# delayed_lfo.net
KiCad netlist of a schematic drawn in EAGLE
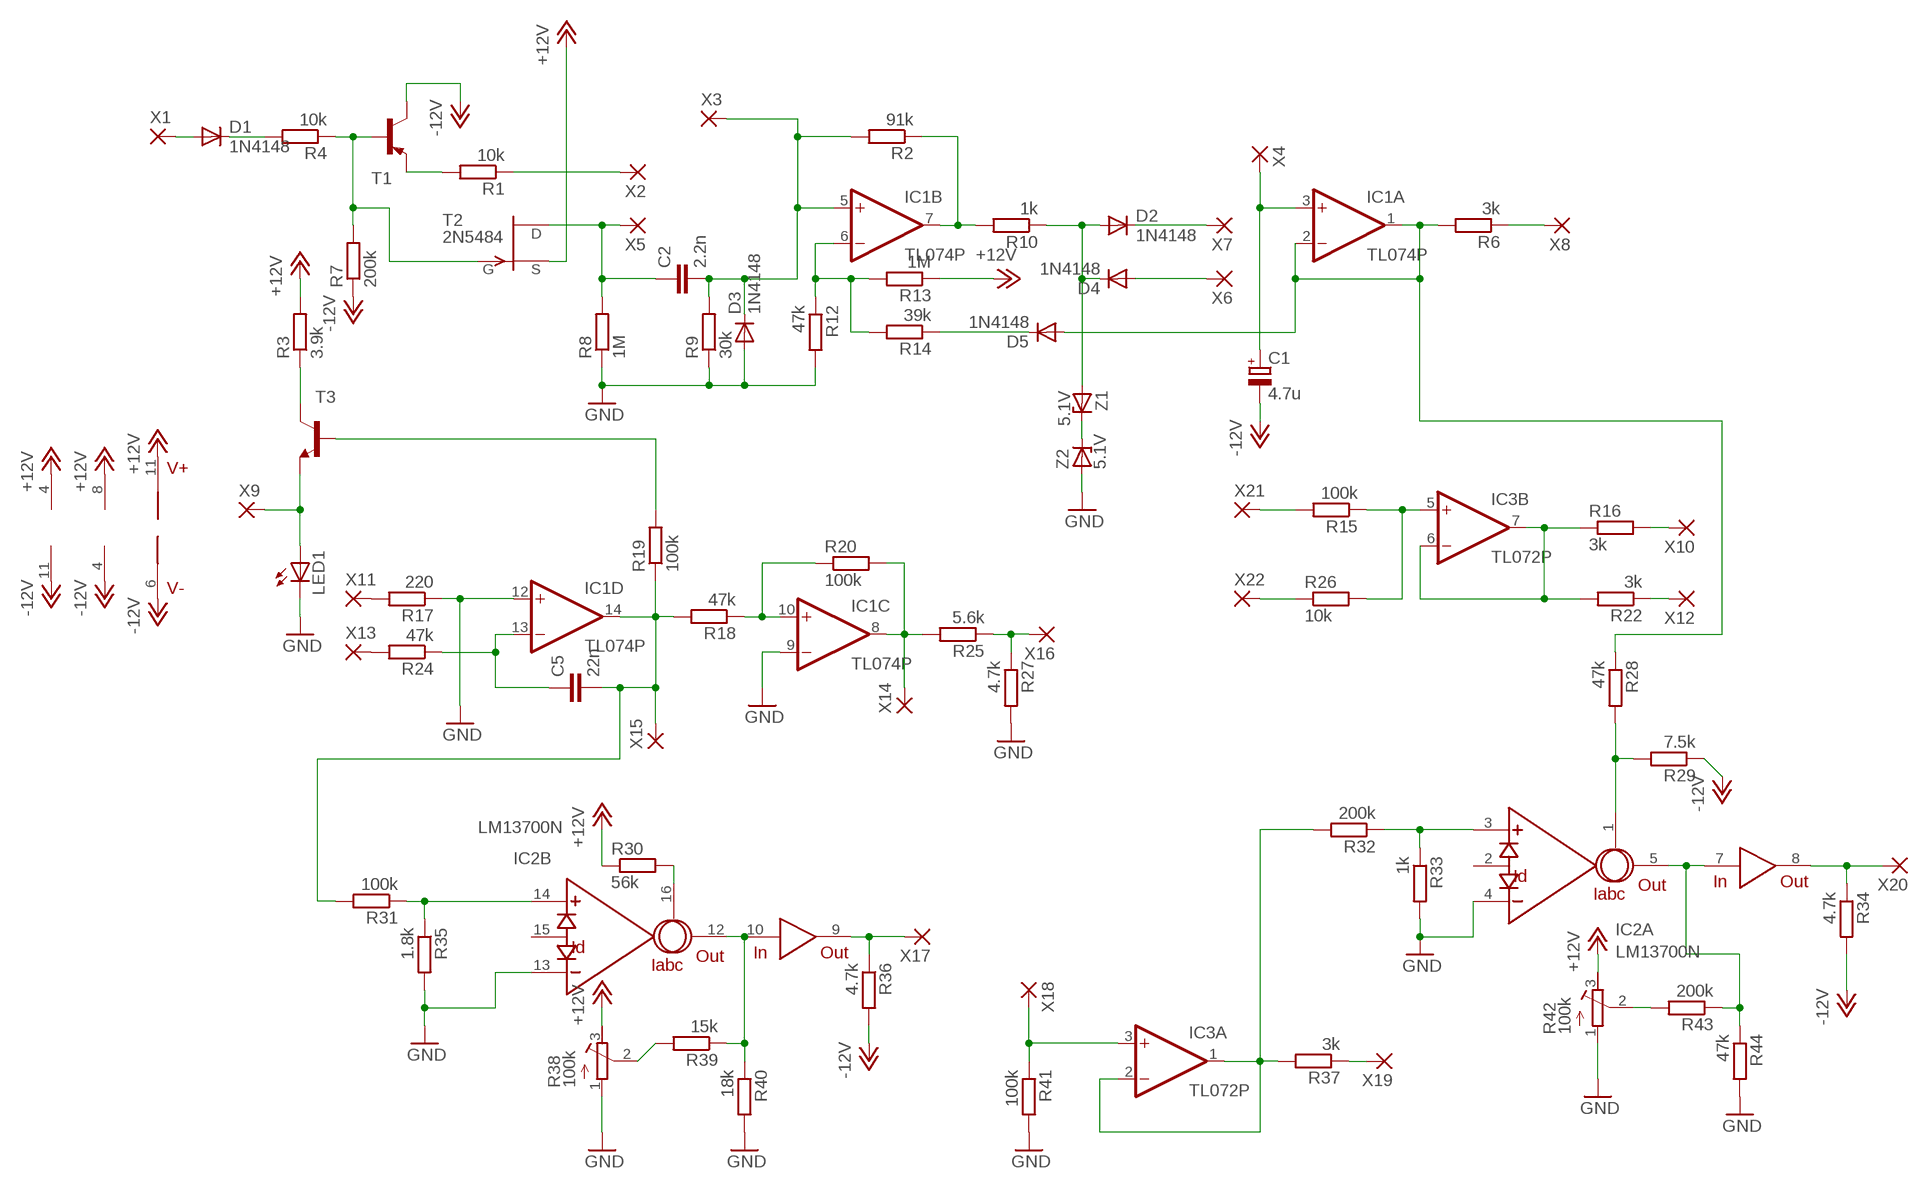
[diagram p0: schematic, sheet 1]
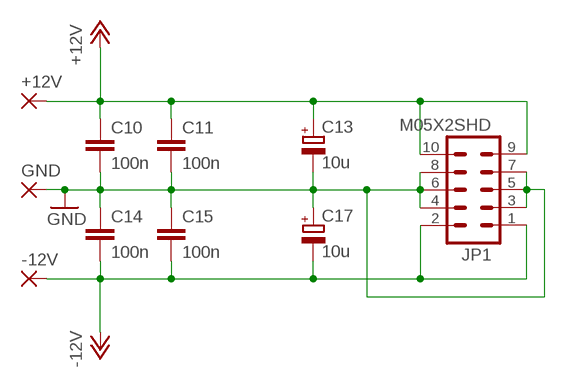
[diagram p1: schematic, sheet 2]

(export (version "E")
  (design (tool "Eeschema 10.0.6"))
  (components
    (comp (ref "+12V")
      (value "2,54/1,0")
      (footprint "eagle-import:2,54_1,0")
      (libsource (lib "eagle-import") (part "2,54/1,0"))
    )
    (comp (ref "-12V")
      (value "2,54/1,0")
      (footprint "eagle-import:2,54_1,0")
      (libsource (lib "eagle-import") (part "2,54/1,0"))
    )
    (comp (ref "C10")
      (value "100n")
      (footprint "eagle-import:C050-035X075")
      (libsource (lib "eagle-import") (part "C-EU050-035X075"))
    )
    (comp (ref "C11")
      (value "100n")
      (footprint "eagle-import:C050-035X075")
      (libsource (lib "eagle-import") (part "C-EU050-035X075"))
    )
    (comp (ref "C13")
      (value "10u")
      (footprint "eagle-import:E3,5-8")
      (libsource (lib "eagle-import") (part "CPOL-EUE3.5-8"))
    )
    (comp (ref "C14")
      (value "100n")
      (footprint "eagle-import:C050-035X075")
      (libsource (lib "eagle-import") (part "C-EU050-035X075"))
    )
    (comp (ref "C15")
      (value "100n")
      (footprint "eagle-import:C050-035X075")
      (libsource (lib "eagle-import") (part "C-EU050-035X075"))
    )
    (comp (ref "C17")
      (value "10u")
      (footprint "eagle-import:E3,5-8")
      (libsource (lib "eagle-import") (part "CPOL-EUE3.5-8"))
    )
    (comp (ref "GND")
      (value "2,54/1,0")
      (footprint "eagle-import:2,54_1,0")
      (libsource (lib "eagle-import") (part "2,54/1,0"))
    )
    (comp (ref "JP1")
      (value "M05X2SHD")
      (footprint "eagle-import:2X5-SHROUDED")
      (libsource (lib "eagle-import") (part "M05X2SHD"))
    )
    (comp (ref "C1")
      (value "4.7u")
      (footprint "eagle-import:E2-5")
      (libsource (lib "eagle-import") (part "CPOL-EUE2-5"))
    )
    (comp (ref "C2")
      (value "2.2n")
      (footprint "eagle-import:C050-035X075")
      (libsource (lib "eagle-import") (part "C-EU050-035X075"))
    )
    (comp (ref "C5")
      (value "22n")
      (footprint "eagle-import:C050-035X075")
      (libsource (lib "eagle-import") (part "C-EU050-035X075"))
    )
    (comp (ref "D1")
      (value "1N4148")
      (footprint "eagle-import:DO35-7")
      (libsource (lib "eagle-import") (part "1N4148DO35-7"))
    )
    (comp (ref "D2")
      (value "1N4148")
      (footprint "eagle-import:DO35-7")
      (libsource (lib "eagle-import") (part "1N4148DO35-7"))
    )
    (comp (ref "D3")
      (value "1N4148")
      (footprint "eagle-import:DO35-7")
      (libsource (lib "eagle-import") (part "1N4148DO35-7"))
    )
    (comp (ref "D4")
      (value "1N4148")
      (footprint "eagle-import:DO35-7")
      (libsource (lib "eagle-import") (part "1N4148DO35-7"))
    )
    (comp (ref "D5")
      (value "1N4148")
      (footprint "eagle-import:DO35-7")
      (libsource (lib "eagle-import") (part "1N4148DO35-7"))
    )
    (comp (ref "IC1")
      (value "TL074P")
      (footprint "eagle-import:DIL14")
      (libsource (lib "eagle-import") (part "TL074P"))
    )
    (comp (ref "IC2")
      (value "LM13700N")
      (footprint "eagle-import:DIL16")
      (libsource (lib "eagle-import") (part "LM13700N"))
    )
    (comp (ref "IC3")
      (value "TL072P")
      (footprint "eagle-import:DIL08")
      (libsource (lib "eagle-import") (part "TL072P"))
    )
    (comp (ref "LED1")
      (value "LED5MM")
      (footprint "eagle-import:LED5MM")
      (libsource (lib "eagle-import") (part "LED5MM"))
    )
    (comp (ref "R1")
      (value "10k")
      (footprint "eagle-import:0309V")
      (libsource (lib "eagle-import") (part "R-EU_0309/V"))
    )
    (comp (ref "R2")
      (value "91k")
      (footprint "eagle-import:0309V")
      (libsource (lib "eagle-import") (part "R-EU_0309/V"))
    )
    (comp (ref "R3")
      (value "3.9k")
      (footprint "eagle-import:0309V")
      (libsource (lib "eagle-import") (part "R-EU_0309/V"))
    )
    (comp (ref "R4")
      (value "10k")
      (footprint "eagle-import:0309V")
      (libsource (lib "eagle-import") (part "R-EU_0309/V"))
    )
    (comp (ref "R6")
      (value "3k")
      (footprint "eagle-import:0309V")
      (libsource (lib "eagle-import") (part "R-EU_0309/V"))
    )
    (comp (ref "R7")
      (value "200k")
      (footprint "eagle-import:0309V")
      (libsource (lib "eagle-import") (part "R-EU_0309/V"))
    )
    (comp (ref "R8")
      (value "1M")
      (footprint "eagle-import:0309V")
      (libsource (lib "eagle-import") (part "R-EU_0309/V"))
    )
    (comp (ref "R9")
      (value "30k")
      (footprint "eagle-import:0309V")
      (libsource (lib "eagle-import") (part "R-EU_0309/V"))
    )
    (comp (ref "R10")
      (value "1k")
      (footprint "eagle-import:0309V")
      (libsource (lib "eagle-import") (part "R-EU_0309/V"))
    )
    (comp (ref "R12")
      (value "47k")
      (footprint "eagle-import:0309V")
      (libsource (lib "eagle-import") (part "R-EU_0309/V"))
    )
    (comp (ref "R13")
      (value "1M")
      (footprint "eagle-import:0309V")
      (libsource (lib "eagle-import") (part "R-EU_0309/V"))
    )
    (comp (ref "R14")
      (value "39k")
      (footprint "eagle-import:0309V")
      (libsource (lib "eagle-import") (part "R-EU_0309/V"))
    )
    (comp (ref "R15")
      (value "100k")
      (footprint "eagle-import:0309V")
      (libsource (lib "eagle-import") (part "R-EU_0309/V"))
    )
    (comp (ref "R16")
      (value "3k")
      (footprint "eagle-import:0309V")
      (libsource (lib "eagle-import") (part "R-EU_0309/V"))
    )
    (comp (ref "R17")
      (value "220")
      (footprint "eagle-import:0309V")
      (libsource (lib "eagle-import") (part "R-EU_0309/V"))
    )
    (comp (ref "R18")
      (value "47k")
      (footprint "eagle-import:0309_10")
      (libsource (lib "eagle-import") (part "R-EU_0309/10"))
    )
    (comp (ref "R19")
      (value "100k")
      (footprint "eagle-import:0309V")
      (libsource (lib "eagle-import") (part "R-EU_0309/V"))
    )
    (comp (ref "R20")
      (value "100k")
      (footprint "eagle-import:0309V")
      (libsource (lib "eagle-import") (part "R-EU_0309/V"))
    )
    (comp (ref "R22")
      (value "3k")
      (footprint "eagle-import:0309V")
      (libsource (lib "eagle-import") (part "R-EU_0309/V"))
    )
    (comp (ref "R24")
      (value "47k")
      (footprint "eagle-import:0309V")
      (libsource (lib "eagle-import") (part "R-EU_0309/V"))
    )
    (comp (ref "R25")
      (value "5.6k")
      (footprint "eagle-import:0309V")
      (libsource (lib "eagle-import") (part "R-EU_0309/V"))
    )
    (comp (ref "R26")
      (value "10k")
      (footprint "eagle-import:0309V")
      (libsource (lib "eagle-import") (part "R-EU_0309/V"))
    )
    (comp (ref "R27")
      (value "4.7k")
      (footprint "eagle-import:0309V")
      (libsource (lib "eagle-import") (part "R-EU_0309/V"))
    )
    (comp (ref "R28")
      (value "47k")
      (footprint "eagle-import:0309V")
      (libsource (lib "eagle-import") (part "R-EU_0309/V"))
    )
    (comp (ref "R29")
      (value "7.5k")
      (footprint "eagle-import:0309V")
      (libsource (lib "eagle-import") (part "R-EU_0309/V"))
    )
    (comp (ref "R30")
      (value "56k")
      (footprint "eagle-import:0309V")
      (libsource (lib "eagle-import") (part "R-EU_0309/V"))
    )
    (comp (ref "R31")
      (value "100k")
      (footprint "eagle-import:0309V")
      (libsource (lib "eagle-import") (part "R-EU_0309/V"))
    )
    (comp (ref "R32")
      (value "200k")
      (footprint "eagle-import:0309_10")
      (libsource (lib "eagle-import") (part "R-EU_0309/10"))
    )
    (comp (ref "R33")
      (value "1k")
      (footprint "eagle-import:0309V")
      (libsource (lib "eagle-import") (part "R-EU_0309/V"))
    )
    (comp (ref "R34")
      (value "4.7k")
      (footprint "eagle-import:0309_10")
      (libsource (lib "eagle-import") (part "R-EU_0309/10"))
    )
    (comp (ref "R35")
      (value "1.8k")
      (footprint "eagle-import:0309V")
      (libsource (lib "eagle-import") (part "R-EU_0309/V"))
    )
    (comp (ref "R36")
      (value "4.7k")
      (footprint "eagle-import:0309_10")
      (libsource (lib "eagle-import") (part "R-EU_0309/10"))
    )
    (comp (ref "R37")
      (value "3k")
      (footprint "eagle-import:0309V")
      (libsource (lib "eagle-import") (part "R-EU_0309/V"))
    )
    (comp (ref "R38")
      (value "100k")
      (footprint "eagle-import:RTRIM64W")
      (libsource (lib "eagle-import") (part "R-TRIMM64W"))
    )
    (comp (ref "R39")
      (value "15k")
      (footprint "eagle-import:0309_10")
      (libsource (lib "eagle-import") (part "R-EU_0309/10"))
    )
    (comp (ref "R40")
      (value "18k")
      (footprint "eagle-import:0309_10")
      (libsource (lib "eagle-import") (part "R-EU_0309/10"))
    )
    (comp (ref "R41")
      (value "100k")
      (footprint "eagle-import:0309_10")
      (libsource (lib "eagle-import") (part "R-EU_0309/10"))
    )
    (comp (ref "R42")
      (value "100k")
      (footprint "eagle-import:RTRIM64W")
      (libsource (lib "eagle-import") (part "R-TRIMM64W"))
    )
    (comp (ref "R43")
      (value "200k")
      (footprint "eagle-import:0309V")
      (libsource (lib "eagle-import") (part "R-EU_0309/V"))
    )
    (comp (ref "R44")
      (value "47k")
      (footprint "eagle-import:0309V")
      (libsource (lib "eagle-import") (part "R-EU_0309/V"))
    )
    (comp (ref "T1")
      (value "2N3906-PNP-TO92-EBC")
      (footprint "eagle-import:TO92-EBC")
      (libsource (lib "eagle-import") (part "-PNP-TO92-EBC2N3906"))
    )
    (comp (ref "T2")
      (value "2N5484")
      (footprint "eagle-import:TO92-")
      (libsource (lib "eagle-import") (part "?5482N4"))
    )
    (comp (ref "T3")
      (value "2N3903-NPN-TO92-BEC")
      (footprint "eagle-import:TO92-BEC")
      (libsource (lib "eagle-import") (part "-NPN-TO92-BEC2N3903"))
    )
    (comp (ref "X1")
      (value "2,54/1,0")
      (footprint "eagle-import:2,54_1,0")
      (libsource (lib "eagle-import") (part "2,54/1,0"))
    )
    (comp (ref "X2")
      (value "2,54/1,0")
      (footprint "eagle-import:2,54_1,0")
      (libsource (lib "eagle-import") (part "2,54/1,0"))
    )
    (comp (ref "X3")
      (value "2,54/1,0")
      (footprint "eagle-import:2,54_1,0")
      (libsource (lib "eagle-import") (part "2,54/1,0"))
    )
    (comp (ref "X4")
      (value "2,54/1,0")
      (footprint "eagle-import:2,54_1,0")
      (libsource (lib "eagle-import") (part "2,54/1,0"))
    )
    (comp (ref "X5")
      (value "2,54/1,0")
      (footprint "eagle-import:2,54_1,0")
      (libsource (lib "eagle-import") (part "2,54/1,0"))
    )
    (comp (ref "X6")
      (value "2,54/1,0")
      (footprint "eagle-import:2,54_1,0")
      (libsource (lib "eagle-import") (part "2,54/1,0"))
    )
    (comp (ref "X7")
      (value "2,54/1,0")
      (footprint "eagle-import:2,54_1,0")
      (libsource (lib "eagle-import") (part "2,54/1,0"))
    )
    (comp (ref "X8")
      (value "2,54/1,0")
      (footprint "eagle-import:2,54_1,0")
      (libsource (lib "eagle-import") (part "2,54/1,0"))
    )
    (comp (ref "X9")
      (value "2,54/1,0")
      (footprint "eagle-import:2,54_1,0")
      (libsource (lib "eagle-import") (part "2,54/1,0"))
    )
    (comp (ref "X10")
      (value "2,54/1,0")
      (footprint "eagle-import:2,54_1,0")
      (libsource (lib "eagle-import") (part "2,54/1,0"))
    )
    (comp (ref "X11")
      (value "2,54/1,0")
      (footprint "eagle-import:2,54_1,0")
      (libsource (lib "eagle-import") (part "2,54/1,0"))
    )
    (comp (ref "X12")
      (value "2,54/1,0")
      (footprint "eagle-import:2,54_1,0")
      (libsource (lib "eagle-import") (part "2,54/1,0"))
    )
    (comp (ref "X13")
      (value "2,54/1,0")
      (footprint "eagle-import:2,54_1,0")
      (libsource (lib "eagle-import") (part "2,54/1,0"))
    )
    (comp (ref "X14")
      (value "2,54/1,0")
      (footprint "eagle-import:2,54_1,0")
      (libsource (lib "eagle-import") (part "2,54/1,0"))
    )
    (comp (ref "X15")
      (value "2,54/1,0")
      (footprint "eagle-import:2,54_1,0")
      (libsource (lib "eagle-import") (part "2,54/1,0"))
    )
    (comp (ref "X16")
      (value "2,54/1,0")
      (footprint "eagle-import:2,54_1,0")
      (libsource (lib "eagle-import") (part "2,54/1,0"))
    )
    (comp (ref "X17")
      (value "2,54/1,0")
      (footprint "eagle-import:2,54_1,0")
      (libsource (lib "eagle-import") (part "2,54/1,0"))
    )
    (comp (ref "X18")
      (value "2,54/1,0")
      (footprint "eagle-import:2,54_1,0")
      (libsource (lib "eagle-import") (part "2,54/1,0"))
    )
    (comp (ref "X19")
      (value "2,54/1,0")
      (footprint "eagle-import:2,54_1,0")
      (libsource (lib "eagle-import") (part "2,54/1,0"))
    )
    (comp (ref "X20")
      (value "2,54/1,0")
      (footprint "eagle-import:2,54_1,0")
      (libsource (lib "eagle-import") (part "2,54/1,0"))
    )
    (comp (ref "X21")
      (value "2,54/1,0")
      (footprint "eagle-import:2,54_1,0")
      (libsource (lib "eagle-import") (part "2,54/1,0"))
    )
    (comp (ref "X22")
      (value "2,54/1,0")
      (footprint "eagle-import:2,54_1,0")
      (libsource (lib "eagle-import") (part "2,54/1,0"))
    )
    (comp (ref "Z1")
      (value "5.1V")
      (footprint "eagle-import:DO34Z7")
      (libsource (lib "eagle-import") (part "BZX90"))
    )
    (comp (ref "Z2")
      (value "5.1V")
      (footprint "eagle-import:DO34Z7")
      (libsource (lib "eagle-import") (part "BZX90"))
    )
  )
  (nets
    (net (code "1") (name "+12V") (class "Default")
      (node (ref "+12V") (pin "1") (pinfunction "P_1") (pintype "passive"))
      (node (ref "C10") (pin "1") (pinfunction "1_1") (pintype "passive"))
      (node (ref "C11") (pin "1") (pinfunction "1_1") (pintype "passive"))
      (node (ref "C13") (pin "+") (pinfunction "+_+") (pintype "passive"))
      (node (ref "IC1") (pin "4") (pinfunction "V+_4") (pintype "power_in"))
      (node (ref "IC2") (pin "11") (pinfunction "V+_11") (pintype "bidirectional"))
      (node (ref "IC3") (pin "8") (pinfunction "V+_8") (pintype "power_in"))
      (node (ref "JP1") (pin "10") (pinfunction "10_10") (pintype "passive"))
      (node (ref "JP1") (pin "9") (pinfunction "9_9") (pintype "passive"))
      (node (ref "R13") (pin "1") (pinfunction "1_1") (pintype "passive"))
      (node (ref "R3") (pin "2") (pinfunction "2_2") (pintype "passive"))
      (node (ref "R30") (pin "1") (pinfunction "1_1") (pintype "passive"))
      (node (ref "R38") (pin "3") (pinfunction "E_3") (pintype "passive"))
      (node (ref "R42") (pin "3") (pinfunction "E_3") (pintype "passive"))
      (node (ref "T2") (pin "2") (pinfunction "S_2") (pintype "passive"))
    )
    (net (code "2") (name "-12V") (class "Default")
      (node (ref "-12V") (pin "1") (pinfunction "P_1") (pintype "passive"))
      (node (ref "C1") (pin "-") (pinfunction "-_-") (pintype "passive"))
      (node (ref "C14") (pin "2") (pinfunction "2_2") (pintype "passive"))
      (node (ref "C15") (pin "2") (pinfunction "2_2") (pintype "passive"))
      (node (ref "C17") (pin "-") (pinfunction "-_-") (pintype "passive"))
      (node (ref "IC1") (pin "11") (pinfunction "V-_11") (pintype "power_in"))
      (node (ref "IC2") (pin "6") (pinfunction "V-_6") (pintype "bidirectional"))
      (node (ref "IC3") (pin "4") (pinfunction "V-_4") (pintype "power_in"))
      (node (ref "JP1") (pin "1") (pinfunction "1_1") (pintype "passive"))
      (node (ref "JP1") (pin "2") (pinfunction "2_2") (pintype "passive"))
      (node (ref "R29") (pin "1") (pinfunction "1_1") (pintype "passive"))
      (node (ref "R34") (pin "2") (pinfunction "2_2") (pintype "passive"))
      (node (ref "R36") (pin "2") (pinfunction "2_2") (pintype "passive"))
      (node (ref "R7") (pin "1") (pinfunction "1_1") (pintype "passive"))
      (node (ref "T1") (pin "C") (pinfunction "C_C") (pintype "passive"))
    )
    (net (code "3") (name "GND") (class "Default")
      (node (ref "C10") (pin "2") (pinfunction "2_2") (pintype "passive"))
      (node (ref "C11") (pin "2") (pinfunction "2_2") (pintype "passive"))
      (node (ref "C13") (pin "-") (pinfunction "-_-") (pintype "passive"))
      (node (ref "C14") (pin "1") (pinfunction "1_1") (pintype "passive"))
      (node (ref "C15") (pin "1") (pinfunction "1_1") (pintype "passive"))
      (node (ref "C17") (pin "+") (pinfunction "+_+") (pintype "passive"))
      (node (ref "D3") (pin "A") (pinfunction "A_A") (pintype "passive"))
      (node (ref "GND") (pin "1") (pinfunction "P_1") (pintype "passive"))
      (node (ref "IC1") (pin "12") (pinfunction "+IN_12") (pintype "input"))
      (node (ref "IC1") (pin "9") (pinfunction "-IN_9") (pintype "input"))
      (node (ref "IC2") (pin "13") (pinfunction "-IN_13") (pintype "bidirectional"))
      (node (ref "IC2") (pin "4") (pinfunction "-IN_4") (pintype "bidirectional"))
      (node (ref "JP1") (pin "3") (pinfunction "3_3") (pintype "passive"))
      (node (ref "JP1") (pin "4") (pinfunction "4_4") (pintype "passive"))
      (node (ref "JP1") (pin "5") (pinfunction "5_5") (pintype "passive"))
      (node (ref "JP1") (pin "6") (pinfunction "6_6") (pintype "passive"))
      (node (ref "JP1") (pin "7") (pinfunction "7_7") (pintype "passive"))
      (node (ref "JP1") (pin "8") (pinfunction "8_8") (pintype "passive"))
      (node (ref "LED1") (pin "K") (pinfunction "C_K") (pintype "passive"))
      (node (ref "R12") (pin "2") (pinfunction "2_2") (pintype "passive"))
      (node (ref "R17") (pin "1") (pinfunction "1_1") (pintype "passive"))
      (node (ref "R27") (pin "2") (pinfunction "2_2") (pintype "passive"))
      (node (ref "R33") (pin "2") (pinfunction "2_2") (pintype "passive"))
      (node (ref "R35") (pin "2") (pinfunction "2_2") (pintype "passive"))
      (node (ref "R38") (pin "1") (pinfunction "A_1") (pintype "passive"))
      (node (ref "R40") (pin "2") (pinfunction "2_2") (pintype "passive"))
      (node (ref "R41") (pin "2") (pinfunction "2_2") (pintype "passive"))
      (node (ref "R42") (pin "1") (pinfunction "A_1") (pintype "passive"))
      (node (ref "R44") (pin "2") (pinfunction "2_2") (pintype "passive"))
      (node (ref "R8") (pin "1") (pinfunction "1_1") (pintype "passive"))
      (node (ref "R9") (pin "1") (pinfunction "1_1") (pintype "passive"))
      (node (ref "Z2") (pin "A") (pinfunction "A_A") (pintype "passive"))
    )
    (net (code "4") (name "Net-(D1-PadC)") (class "Default")
      (node (ref "D1") (pin "C") (pinfunction "C_C") (pintype "passive"))
      (node (ref "R4") (pin "2") (pinfunction "2_2") (pintype "passive"))
    )
    (net (code "5") (name "Net-(D2-PadA)") (class "Default")
      (node (ref "D2") (pin "A") (pinfunction "A_A") (pintype "passive"))
      (node (ref "D4") (pin "C") (pinfunction "C_C") (pintype "passive"))
      (node (ref "R10") (pin "1") (pinfunction "1_1") (pintype "passive"))
      (node (ref "Z1") (pin "A") (pinfunction "A_A") (pintype "passive"))
    )
    (net (code "6") (name "Net-(D5-PadC)") (class "Default")
      (node (ref "D5") (pin "C") (pinfunction "C_C") (pintype "passive"))
      (node (ref "R14") (pin "1") (pinfunction "1_1") (pintype "passive"))
    )
    (net (code "7") (name "Net-(IC1A-+IN)") (class "Default")
      (node (ref "C1") (pin "+") (pinfunction "+_+") (pintype "passive"))
      (node (ref "IC1") (pin "3") (pinfunction "+IN_3") (pintype "input"))
      (node (ref "X4") (pin "1") (pinfunction "P_1") (pintype "passive"))
    )
    (net (code "8") (name "Net-(IC1A--IN)") (class "Default")
      (node (ref "D5") (pin "A") (pinfunction "A_A") (pintype "passive"))
      (node (ref "IC1") (pin "1") (pinfunction "OUT_1") (pintype "output"))
      (node (ref "IC1") (pin "2") (pinfunction "-IN_2") (pintype "input"))
      (node (ref "R28") (pin "1") (pinfunction "1_1") (pintype "passive"))
      (node (ref "R6") (pin "2") (pinfunction "2_2") (pintype "passive"))
    )
    (net (code "9") (name "Net-(IC1B-+IN)") (class "Default")
      (node (ref "C2") (pin "2") (pinfunction "2_2") (pintype "passive"))
      (node (ref "D3") (pin "C") (pinfunction "C_C") (pintype "passive"))
      (node (ref "IC1") (pin "5") (pinfunction "+IN_5") (pintype "input"))
      (node (ref "R2") (pin "2") (pinfunction "2_2") (pintype "passive"))
      (node (ref "R9") (pin "2") (pinfunction "2_2") (pintype "passive"))
      (node (ref "X3") (pin "1") (pinfunction "P_1") (pintype "passive"))
    )
    (net (code "10") (name "Net-(IC1B--IN)") (class "Default")
      (node (ref "IC1") (pin "6") (pinfunction "-IN_6") (pintype "input"))
      (node (ref "R12") (pin "1") (pinfunction "1_1") (pintype "passive"))
      (node (ref "R13") (pin "2") (pinfunction "2_2") (pintype "passive"))
      (node (ref "R14") (pin "2") (pinfunction "2_2") (pintype "passive"))
    )
    (net (code "11") (name "Net-(IC1B-OUT)") (class "Default")
      (node (ref "IC1") (pin "7") (pinfunction "OUT_7") (pintype "output"))
      (node (ref "R10") (pin "2") (pinfunction "2_2") (pintype "passive"))
      (node (ref "R2") (pin "1") (pinfunction "1_1") (pintype "passive"))
    )
    (net (code "12") (name "Net-(IC1C-+IN)") (class "Default")
      (node (ref "IC1") (pin "10") (pinfunction "+IN_10") (pintype "input"))
      (node (ref "R18") (pin "1") (pinfunction "1_1") (pintype "passive"))
      (node (ref "R20") (pin "1") (pinfunction "1_1") (pintype "passive"))
    )
    (net (code "13") (name "Net-(IC1C-OUT)") (class "Default")
      (node (ref "IC1") (pin "8") (pinfunction "OUT_8") (pintype "output"))
      (node (ref "R20") (pin "2") (pinfunction "2_2") (pintype "passive"))
      (node (ref "R25") (pin "2") (pinfunction "2_2") (pintype "passive"))
      (node (ref "X14") (pin "1") (pinfunction "P_1") (pintype "passive"))
    )
    (net (code "14") (name "Net-(IC1D--IN)") (class "Default")
      (node (ref "C5") (pin "1") (pinfunction "1_1") (pintype "passive"))
      (node (ref "IC1") (pin "13") (pinfunction "-IN_13") (pintype "input"))
      (node (ref "R24") (pin "1") (pinfunction "1_1") (pintype "passive"))
    )
    (net (code "15") (name "Net-(IC1D-OUT)") (class "Default")
      (node (ref "C5") (pin "2") (pinfunction "2_2") (pintype "passive"))
      (node (ref "IC1") (pin "14") (pinfunction "OUT_14") (pintype "output"))
      (node (ref "R18") (pin "2") (pinfunction "2_2") (pintype "passive"))
      (node (ref "R19") (pin "1") (pinfunction "1_1") (pintype "passive"))
      (node (ref "R31") (pin "2") (pinfunction "2_2") (pintype "passive"))
      (node (ref "X15") (pin "1") (pinfunction "P_1") (pintype "passive"))
    )
    (net (code "16") (name "Net-(IC2A-+IN)") (class "Default")
      (node (ref "IC2") (pin "3") (pinfunction "+IN_3") (pintype "bidirectional"))
      (node (ref "R32") (pin "1") (pinfunction "1_1") (pintype "passive"))
      (node (ref "R33") (pin "1") (pinfunction "1_1") (pintype "passive"))
    )
    (net (code "17") (name "Net-(IC2A-IABC)") (class "Default")
      (node (ref "IC2") (pin "1") (pinfunction "IABC_1") (pintype "bidirectional"))
      (node (ref "R28") (pin "2") (pinfunction "2_2") (pintype "passive"))
      (node (ref "R29") (pin "2") (pinfunction "2_2") (pintype "passive"))
    )
    (net (code "18") (name "Net-(IC2A-OUT)") (class "Default")
      (node (ref "IC2") (pin "5") (pinfunction "OUT_5") (pintype "bidirectional"))
      (node (ref "IC2") (pin "7") (pinfunction "IN_7") (pintype "bidirectional"))
      (node (ref "R43") (pin "1") (pinfunction "1_1") (pintype "passive"))
      (node (ref "R44") (pin "1") (pinfunction "1_1") (pintype "passive"))
    )
    (net (code "19") (name "Net-(IC2B-+IN)") (class "Default")
      (node (ref "IC2") (pin "14") (pinfunction "+IN_14") (pintype "bidirectional"))
      (node (ref "R31") (pin "1") (pinfunction "1_1") (pintype "passive"))
      (node (ref "R35") (pin "1") (pinfunction "1_1") (pintype "passive"))
    )
    (net (code "20") (name "Net-(IC2B-IABC)") (class "Default")
      (node (ref "IC2") (pin "16") (pinfunction "IABC_16") (pintype "bidirectional"))
      (node (ref "R30") (pin "2") (pinfunction "2_2") (pintype "passive"))
    )
    (net (code "21") (name "Net-(IC2B-OUT)") (class "Default")
      (node (ref "IC2") (pin "10") (pinfunction "IN_10") (pintype "bidirectional"))
      (node (ref "IC2") (pin "12") (pinfunction "OUT_12") (pintype "bidirectional"))
      (node (ref "R39") (pin "1") (pinfunction "1_1") (pintype "passive"))
      (node (ref "R40") (pin "1") (pinfunction "1_1") (pintype "passive"))
    )
    (net (code "22") (name "Net-(IC2C-OUT)") (class "Default")
      (node (ref "IC2") (pin "8") (pinfunction "OUT_8") (pintype "bidirectional"))
      (node (ref "R34") (pin "1") (pinfunction "1_1") (pintype "passive"))
      (node (ref "X20") (pin "1") (pinfunction "P_1") (pintype "passive"))
    )
    (net (code "23") (name "Net-(IC2D-OUT)") (class "Default")
      (node (ref "IC2") (pin "9") (pinfunction "OUT_9") (pintype "bidirectional"))
      (node (ref "R36") (pin "1") (pinfunction "1_1") (pintype "passive"))
      (node (ref "X17") (pin "1") (pinfunction "P_1") (pintype "passive"))
    )
    (net (code "24") (name "Net-(IC3A-+IN)") (class "Default")
      (node (ref "IC3") (pin "3") (pinfunction "+IN_3") (pintype "input"))
      (node (ref "R41") (pin "1") (pinfunction "1_1") (pintype "passive"))
      (node (ref "X18") (pin "1") (pinfunction "P_1") (pintype "passive"))
    )
    (net (code "25") (name "Net-(IC3A--IN)") (class "Default")
      (node (ref "IC3") (pin "1") (pinfunction "OUT_1") (pintype "output"))
      (node (ref "IC3") (pin "2") (pinfunction "-IN_2") (pintype "input"))
      (node (ref "R32") (pin "2") (pinfunction "2_2") (pintype "passive"))
      (node (ref "R37") (pin "2") (pinfunction "2_2") (pintype "passive"))
    )
    (net (code "26") (name "Net-(IC3B-+IN)") (class "Default")
      (node (ref "IC3") (pin "5") (pinfunction "+IN_5") (pintype "input"))
      (node (ref "R15") (pin "1") (pinfunction "1_1") (pintype "passive"))
      (node (ref "R26") (pin "2") (pinfunction "2_2") (pintype "passive"))
    )
    (net (code "27") (name "Net-(IC3B--IN)") (class "Default")
      (node (ref "IC3") (pin "6") (pinfunction "-IN_6") (pintype "input"))
      (node (ref "IC3") (pin "7") (pinfunction "OUT_7") (pintype "output"))
      (node (ref "R16") (pin "1") (pinfunction "1_1") (pintype "passive"))
      (node (ref "R22") (pin "2") (pinfunction "2_2") (pintype "passive"))
    )
    (net (code "28") (name "Net-(R1-Pad2)") (class "Default")
      (node (ref "R1") (pin "2") (pinfunction "2_2") (pintype "passive"))
      (node (ref "T1") (pin "E") (pinfunction "E_E") (pintype "passive"))
    )
    (net (code "29") (name "Net-(R3-Pad1)") (class "Default")
      (node (ref "R3") (pin "1") (pinfunction "1_1") (pintype "passive"))
      (node (ref "T3") (pin "C") (pinfunction "C_C") (pintype "passive"))
    )
    (net (code "30") (name "Net-(R19-Pad2)") (class "Default")
      (node (ref "R19") (pin "2") (pinfunction "2_2") (pintype "passive"))
      (node (ref "T3") (pin "B") (pinfunction "B_B") (pintype "passive"))
    )
    (net (code "31") (name "Net-(R38-S)") (class "Default")
      (node (ref "R38") (pin "2") (pinfunction "S_2") (pintype "passive"))
      (node (ref "R39") (pin "2") (pinfunction "2_2") (pintype "passive"))
    )
    (net (code "32") (name "Net-(R42-S)") (class "Default")
      (node (ref "R42") (pin "2") (pinfunction "S_2") (pintype "passive"))
      (node (ref "R43") (pin "2") (pinfunction "2_2") (pintype "passive"))
    )
    (net (code "33") (name "Net-(T2-D)") (class "Default")
      (node (ref "C2") (pin "1") (pinfunction "1_1") (pintype "passive"))
      (node (ref "R8") (pin "2") (pinfunction "2_2") (pintype "passive"))
      (node (ref "T2") (pin "3") (pinfunction "D_3") (pintype "passive"))
      (node (ref "X5") (pin "1") (pinfunction "P_1") (pintype "passive"))
    )
    (net (code "34") (name "Net-(T2-G)") (class "Default")
      (node (ref "R4") (pin "1") (pinfunction "1_1") (pintype "passive"))
      (node (ref "R7") (pin "2") (pinfunction "2_2") (pintype "passive"))
      (node (ref "T1") (pin "B") (pinfunction "B_B") (pintype "passive"))
      (node (ref "T2") (pin "1") (pinfunction "G_1") (pintype "passive"))
    )
    (net (code "35") (name "Net-(X1-P)") (class "Default")
      (node (ref "D1") (pin "A") (pinfunction "A_A") (pintype "passive"))
      (node (ref "X1") (pin "1") (pinfunction "P_1") (pintype "passive"))
    )
    (net (code "36") (name "Net-(X2-P)") (class "Default")
      (node (ref "R1") (pin "1") (pinfunction "1_1") (pintype "passive"))
      (node (ref "X2") (pin "1") (pinfunction "P_1") (pintype "passive"))
    )
    (net (code "37") (name "Net-(X6-P)") (class "Default")
      (node (ref "D4") (pin "A") (pinfunction "A_A") (pintype "passive"))
      (node (ref "X6") (pin "1") (pinfunction "P_1") (pintype "passive"))
    )
    (net (code "38") (name "Net-(X7-P)") (class "Default")
      (node (ref "D2") (pin "C") (pinfunction "C_C") (pintype "passive"))
      (node (ref "X7") (pin "1") (pinfunction "P_1") (pintype "passive"))
    )
    (net (code "39") (name "Net-(X8-P)") (class "Default")
      (node (ref "R6") (pin "1") (pinfunction "1_1") (pintype "passive"))
      (node (ref "X8") (pin "1") (pinfunction "P_1") (pintype "passive"))
    )
    (net (code "40") (name "Net-(X9-P)") (class "Default")
      (node (ref "LED1") (pin "A") (pinfunction "A_A") (pintype "passive"))
      (node (ref "T3") (pin "E") (pinfunction "E_E") (pintype "passive"))
      (node (ref "X9") (pin "1") (pinfunction "P_1") (pintype "passive"))
    )
    (net (code "41") (name "Net-(X10-P)") (class "Default")
      (node (ref "R16") (pin "2") (pinfunction "2_2") (pintype "passive"))
      (node (ref "X10") (pin "1") (pinfunction "P_1") (pintype "passive"))
    )
    (net (code "42") (name "Net-(X11-P)") (class "Default")
      (node (ref "R17") (pin "2") (pinfunction "2_2") (pintype "passive"))
      (node (ref "X11") (pin "1") (pinfunction "P_1") (pintype "passive"))
    )
    (net (code "43") (name "Net-(X12-P)") (class "Default")
      (node (ref "R22") (pin "1") (pinfunction "1_1") (pintype "passive"))
      (node (ref "X12") (pin "1") (pinfunction "P_1") (pintype "passive"))
    )
    (net (code "44") (name "Net-(X13-P)") (class "Default")
      (node (ref "R24") (pin "2") (pinfunction "2_2") (pintype "passive"))
      (node (ref "X13") (pin "1") (pinfunction "P_1") (pintype "passive"))
    )
    (net (code "45") (name "Net-(X16-P)") (class "Default")
      (node (ref "R25") (pin "1") (pinfunction "1_1") (pintype "passive"))
      (node (ref "R27") (pin "1") (pinfunction "1_1") (pintype "passive"))
      (node (ref "X16") (pin "1") (pinfunction "P_1") (pintype "passive"))
    )
    (net (code "46") (name "Net-(X19-P)") (class "Default")
      (node (ref "R37") (pin "1") (pinfunction "1_1") (pintype "passive"))
      (node (ref "X19") (pin "1") (pinfunction "P_1") (pintype "passive"))
    )
    (net (code "47") (name "Net-(X21-P)") (class "Default")
      (node (ref "R15") (pin "2") (pinfunction "2_2") (pintype "passive"))
      (node (ref "X21") (pin "1") (pinfunction "P_1") (pintype "passive"))
    )
    (net (code "48") (name "Net-(X22-P)") (class "Default")
      (node (ref "R26") (pin "1") (pinfunction "1_1") (pintype "passive"))
      (node (ref "X22") (pin "1") (pinfunction "P_1") (pintype "passive"))
    )
    (net (code "49") (name "Net-(Z1-PadC)") (class "Default")
      (node (ref "Z1") (pin "C") (pinfunction "C_C") (pintype "passive"))
      (node (ref "Z2") (pin "C") (pinfunction "C_C") (pintype "passive"))
    )
    (net (code "50") (name "unconnected-(IC2A-ID-Pad2)") (class "Default")
      (node (ref "IC2") (pin "2") (pinfunction "ID_2") (pintype "bidirectional"))
    )
    (net (code "51") (name "unconnected-(IC2B-ID-Pad15)") (class "Default")
      (node (ref "IC2") (pin "15") (pinfunction "ID_15") (pintype "bidirectional"))
    )
  )
)
